# W078.net
KiCad netlist of a schematic drawn in EAGLE
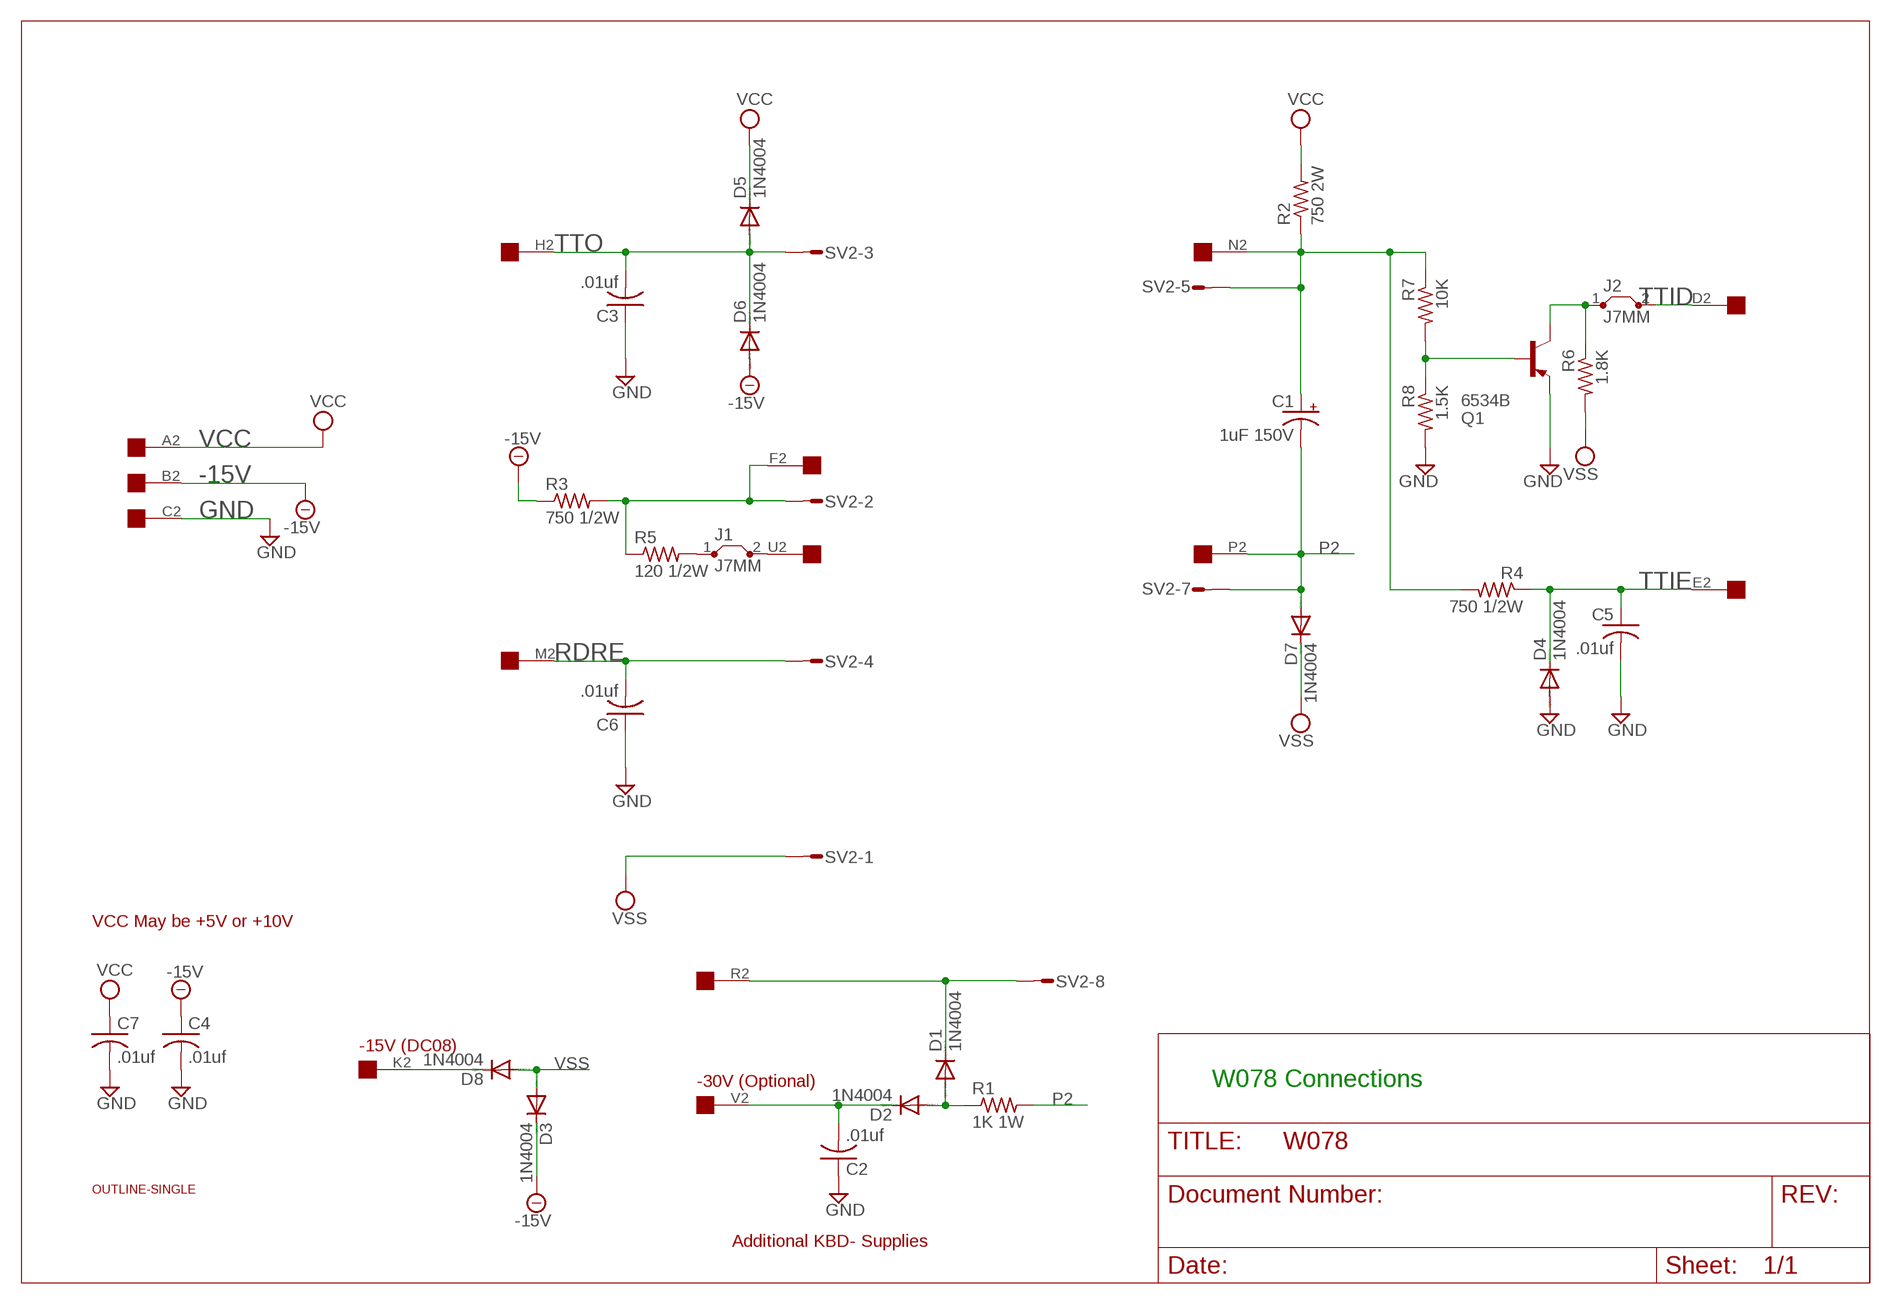
[diagram p0: schematic, sheet 1]

(export (version "E")
  (design (tool "Eeschema 10.0.6"))
  (components
    (comp (ref "C1")
      (value "1uF 150V")
      (footprint "eagle-import:E22-6")
      (libsource (lib "eagle-import") (part "CPOL-USE22-6AXIAL"))
    )
    (comp (ref "C2")
      (value ".01uf")
      (footprint "eagle-import:C050-025X075")
      (libsource (lib "eagle-import") (part "C-US050-025X075"))
    )
    (comp (ref "C3")
      (value ".01uf")
      (footprint "eagle-import:C050-025X075")
      (libsource (lib "eagle-import") (part "C-US050-025X075"))
    )
    (comp (ref "C4")
      (value ".01uf")
      (footprint "eagle-import:C050-025X075")
      (libsource (lib "eagle-import") (part "C-US050-025X075"))
    )
    (comp (ref "C5")
      (value ".01uf")
      (footprint "eagle-import:C050-025X075")
      (libsource (lib "eagle-import") (part "C-US050-025X075"))
    )
    (comp (ref "C6")
      (value ".01uf")
      (footprint "eagle-import:C050-025X075")
      (libsource (lib "eagle-import") (part "C-US050-025X075"))
    )
    (comp (ref "C7")
      (value ".01uf")
      (footprint "eagle-import:C050-025X075")
      (libsource (lib "eagle-import") (part "C-US050-025X075"))
    )
    (comp (ref "D1")
      (value "1N4004")
      (footprint "eagle-import:DO35-10")
      (libsource (lib "eagle-import") (part "1N4148DO35-10"))
    )
    (comp (ref "D2")
      (value "1N4004")
      (footprint "eagle-import:DO35-10")
      (libsource (lib "eagle-import") (part "1N4148DO35-10"))
    )
    (comp (ref "D3")
      (value "1N4004")
      (footprint "eagle-import:DO35-10")
      (libsource (lib "eagle-import") (part "1N4148DO35-10"))
    )
    (comp (ref "D4")
      (value "1N4004")
      (footprint "eagle-import:DO35-10")
      (libsource (lib "eagle-import") (part "1N4148DO35-10"))
    )
    (comp (ref "D5")
      (value "1N4004")
      (footprint "eagle-import:DO35-10")
      (libsource (lib "eagle-import") (part "1N4148DO35-10"))
    )
    (comp (ref "D6")
      (value "1N4004")
      (footprint "eagle-import:DO35-10")
      (libsource (lib "eagle-import") (part "1N4148DO35-10"))
    )
    (comp (ref "D7")
      (value "1N4004")
      (footprint "eagle-import:DO35-10")
      (libsource (lib "eagle-import") (part "1N4148DO35-10"))
    )
    (comp (ref "D8")
      (value "1N4004")
      (footprint "eagle-import:DO35-10")
      (libsource (lib "eagle-import") (part "1N4148DO35-10"))
    )
    (comp (ref "EDGE")
      (value "EDGE-1")
      (footprint "eagle-import:EDGE-CON1")
      (libsource (lib "eagle-import") (part "EDGE-1"))
    )
    (comp (ref "J1")
      (value "J7MM")
      (footprint "eagle-import:07")
      (libsource (lib "eagle-import") (part "J7MM"))
    )
    (comp (ref "J2")
      (value "J7MM")
      (footprint "eagle-import:07")
      (libsource (lib "eagle-import") (part "J7MM"))
    )
    (comp (ref "Q1")
      (value "6534B")
      (footprint "eagle-import:TO92_")
      (libsource (lib "eagle-import") (part "-PNP-TO92/"))
    )
    (comp (ref "R1")
      (value "1K 1W")
      (footprint "eagle-import:0411_15")
      (libsource (lib "eagle-import") (part "R-US_0411/15"))
    )
    (comp (ref "R2")
      (value "750 2W")
      (footprint "eagle-import:0411_15")
      (libsource (lib "eagle-import") (part "R-US_0411/15"))
    )
    (comp (ref "R3")
      (value "750 1/2W")
      (footprint "eagle-import:0309_12")
      (libsource (lib "eagle-import") (part "R-US_0309/12"))
    )
    (comp (ref "R4")
      (value "750 1/2W")
      (footprint "eagle-import:0309_12")
      (libsource (lib "eagle-import") (part "R-US_0309/12"))
    )
    (comp (ref "R5")
      (value "120 1/2W")
      (footprint "eagle-import:0309_12")
      (libsource (lib "eagle-import") (part "R-US_0309/12"))
    )
    (comp (ref "R6")
      (value "1.8K")
      (footprint "eagle-import:0207_10")
      (libsource (lib "eagle-import") (part "R-US_0207/10"))
    )
    (comp (ref "R7")
      (value "10K")
      (footprint "eagle-import:0207_10")
      (libsource (lib "eagle-import") (part "R-US_0207/10"))
    )
    (comp (ref "R8")
      (value "1.5K")
      (footprint "eagle-import:0207_10")
      (libsource (lib "eagle-import") (part "R-US_0207/10"))
    )
    (comp (ref "SV2")
      (value "L08P")
      (footprint "eagle-import:L08P")
      (libsource (lib "eagle-import") (part "L08P"))
    )
    (comp (ref "U$1")
      (value "OUTLINE-SINGLE")
      (footprint "eagle-import:SINGLE")
      (libsource (lib "eagle-import") (part "OUTLINE-SINGLE"))
    )
  )
  (nets
    (net (code "1") (name "-15V") (class "Default")
      (node (ref "C4") (pin "1") (pinfunction "1_1") (pintype "passive"))
      (node (ref "D3") (pin "C") (pinfunction "C_C") (pintype "passive"))
      (node (ref "D6") (pin "A") (pinfunction "A_A") (pintype "passive"))
      (node (ref "EDGE") (pin "B2") (pinfunction "1_B2") (pintype "bidirectional"))
      (node (ref "R3") (pin "1") (pinfunction "1_1") (pintype "passive"))
    )
    (net (code "2") (name "/P2") (class "Default")
      (node (ref "C1") (pin "-") (pinfunction "-_-") (pintype "passive"))
      (node (ref "D7") (pin "A") (pinfunction "A_A") (pintype "passive"))
      (node (ref "EDGE") (pin "P2") (pinfunction "1_P2") (pintype "bidirectional"))
      (node (ref "R1") (pin "2") (pinfunction "2_2") (pintype "passive"))
      (node (ref "SV2") (pin "7") (pinfunction "S_7") (pintype "passive"))
    )
    (net (code "3") (name "/RDRE") (class "Default")
      (node (ref "C6") (pin "2") (pinfunction "2_2") (pintype "passive"))
      (node (ref "EDGE") (pin "M2") (pinfunction "1_M2") (pintype "bidirectional"))
      (node (ref "SV2") (pin "4") (pinfunction "S_4") (pintype "passive"))
    )
    (net (code "4") (name "/TTID") (class "Default")
      (node (ref "EDGE") (pin "D2") (pinfunction "1_D2") (pintype "bidirectional"))
      (node (ref "J2") (pin "2") (pinfunction "2_2") (pintype "passive"))
    )
    (net (code "5") (name "/TTIE") (class "Default")
      (node (ref "C5") (pin "1") (pinfunction "1_1") (pintype "passive"))
      (node (ref "D4") (pin "C") (pinfunction "C_C") (pintype "passive"))
      (node (ref "EDGE") (pin "E2") (pinfunction "1_E2") (pintype "bidirectional"))
      (node (ref "R4") (pin "1") (pinfunction "1_1") (pintype "passive"))
    )
    (net (code "6") (name "/TTO") (class "Default")
      (node (ref "C3") (pin "2") (pinfunction "2_2") (pintype "passive"))
      (node (ref "D5") (pin "A") (pinfunction "A_A") (pintype "passive"))
      (node (ref "D6") (pin "C") (pinfunction "C_C") (pintype "passive"))
      (node (ref "EDGE") (pin "H2") (pinfunction "1_H2") (pintype "bidirectional"))
      (node (ref "SV2") (pin "3") (pinfunction "S_3") (pintype "passive"))
    )
    (net (code "7") (name "GND") (class "Default")
      (node (ref "C2") (pin "1") (pinfunction "1_1") (pintype "passive"))
      (node (ref "C3") (pin "1") (pinfunction "1_1") (pintype "passive"))
      (node (ref "C4") (pin "2") (pinfunction "2_2") (pintype "passive"))
      (node (ref "C5") (pin "2") (pinfunction "2_2") (pintype "passive"))
      (node (ref "C6") (pin "1") (pinfunction "1_1") (pintype "passive"))
      (node (ref "C7") (pin "2") (pinfunction "2_2") (pintype "passive"))
      (node (ref "D4") (pin "A") (pinfunction "A_A") (pintype "passive"))
      (node (ref "EDGE") (pin "C2") (pinfunction "1_C2") (pintype "bidirectional"))
      (node (ref "Q1") (pin "1") (pinfunction "E_1") (pintype "passive"))
      (node (ref "R8") (pin "2") (pinfunction "2_2") (pintype "passive"))
    )
    (net (code "8") (name "Net-(D1-PadA)") (class "Default")
      (node (ref "D1") (pin "A") (pinfunction "A_A") (pintype "passive"))
      (node (ref "D2") (pin "A") (pinfunction "A_A") (pintype "passive"))
      (node (ref "R1") (pin "1") (pinfunction "1_1") (pintype "passive"))
    )
    (net (code "9") (name "Net-(EDGEF-1)") (class "Default")
      (node (ref "EDGE") (pin "F2") (pinfunction "1_F2") (pintype "bidirectional"))
      (node (ref "R3") (pin "2") (pinfunction "2_2") (pintype "passive"))
      (node (ref "R5") (pin "1") (pinfunction "1_1") (pintype "passive"))
      (node (ref "SV2") (pin "2") (pinfunction "S_2") (pintype "passive"))
    )
    (net (code "10") (name "Net-(EDGEI-1)") (class "Default")
      (node (ref "D8") (pin "C") (pinfunction "C_C") (pintype "passive"))
      (node (ref "EDGE") (pin "K2") (pinfunction "1_K2") (pintype "bidirectional"))
    )
    (net (code "11") (name "Net-(EDGEL-1)") (class "Default")
      (node (ref "C1") (pin "+") (pinfunction "+_+") (pintype "passive"))
      (node (ref "EDGE") (pin "N2") (pinfunction "1_N2") (pintype "bidirectional"))
      (node (ref "R2") (pin "1") (pinfunction "1_1") (pintype "passive"))
      (node (ref "R4") (pin "2") (pinfunction "2_2") (pintype "passive"))
      (node (ref "R7") (pin "1") (pinfunction "1_1") (pintype "passive"))
      (node (ref "SV2") (pin "5") (pinfunction "S_5") (pintype "passive"))
    )
    (net (code "12") (name "Net-(EDGEN-1)") (class "Default")
      (node (ref "D1") (pin "C") (pinfunction "C_C") (pintype "passive"))
      (node (ref "EDGE") (pin "R2") (pinfunction "1_R2") (pintype "bidirectional"))
      (node (ref "SV2") (pin "8") (pinfunction "S_8") (pintype "passive"))
    )
    (net (code "13") (name "Net-(EDGEQ-1)") (class "Default")
      (node (ref "EDGE") (pin "U2") (pinfunction "1_U2") (pintype "bidirectional"))
      (node (ref "J1") (pin "2") (pinfunction "2_2") (pintype "passive"))
    )
    (net (code "14") (name "Net-(EDGER-1)") (class "Default")
      (node (ref "C2") (pin "2") (pinfunction "2_2") (pintype "passive"))
      (node (ref "D2") (pin "C") (pinfunction "C_C") (pintype "passive"))
      (node (ref "EDGE") (pin "V2") (pinfunction "1_V2") (pintype "bidirectional"))
    )
    (net (code "15") (name "Net-(J1-Pad1)") (class "Default")
      (node (ref "J1") (pin "1") (pinfunction "1_1") (pintype "passive"))
      (node (ref "R5") (pin "2") (pinfunction "2_2") (pintype "passive"))
    )
    (net (code "16") (name "Net-(Q1-B)") (class "Default")
      (node (ref "Q1") (pin "2") (pinfunction "B_2") (pintype "passive"))
      (node (ref "R7") (pin "2") (pinfunction "2_2") (pintype "passive"))
      (node (ref "R8") (pin "1") (pinfunction "1_1") (pintype "passive"))
    )
    (net (code "17") (name "Net-(Q1-C)") (class "Default")
      (node (ref "J2") (pin "1") (pinfunction "1_1") (pintype "passive"))
      (node (ref "Q1") (pin "3") (pinfunction "C_3") (pintype "passive"))
      (node (ref "R6") (pin "1") (pinfunction "1_1") (pintype "passive"))
    )
    (net (code "18") (name "VCC") (class "Default")
      (node (ref "C7") (pin "1") (pinfunction "1_1") (pintype "passive"))
      (node (ref "D5") (pin "C") (pinfunction "C_C") (pintype "passive"))
      (node (ref "EDGE") (pin "A2") (pinfunction "1_A2") (pintype "bidirectional"))
      (node (ref "R2") (pin "2") (pinfunction "2_2") (pintype "passive"))
    )
    (net (code "19") (name "VSS") (class "Default")
      (node (ref "D3") (pin "A") (pinfunction "A_A") (pintype "passive"))
      (node (ref "D7") (pin "C") (pinfunction "C_C") (pintype "passive"))
      (node (ref "D8") (pin "A") (pinfunction "A_A") (pintype "passive"))
      (node (ref "R6") (pin "2") (pinfunction "2_2") (pintype "passive"))
      (node (ref "SV2") (pin "1") (pinfunction "S_1") (pintype "passive"))
    )
  )
)
